# CONNECTORS.net
KiCad netlist of a schematic drawn in Altium Designer
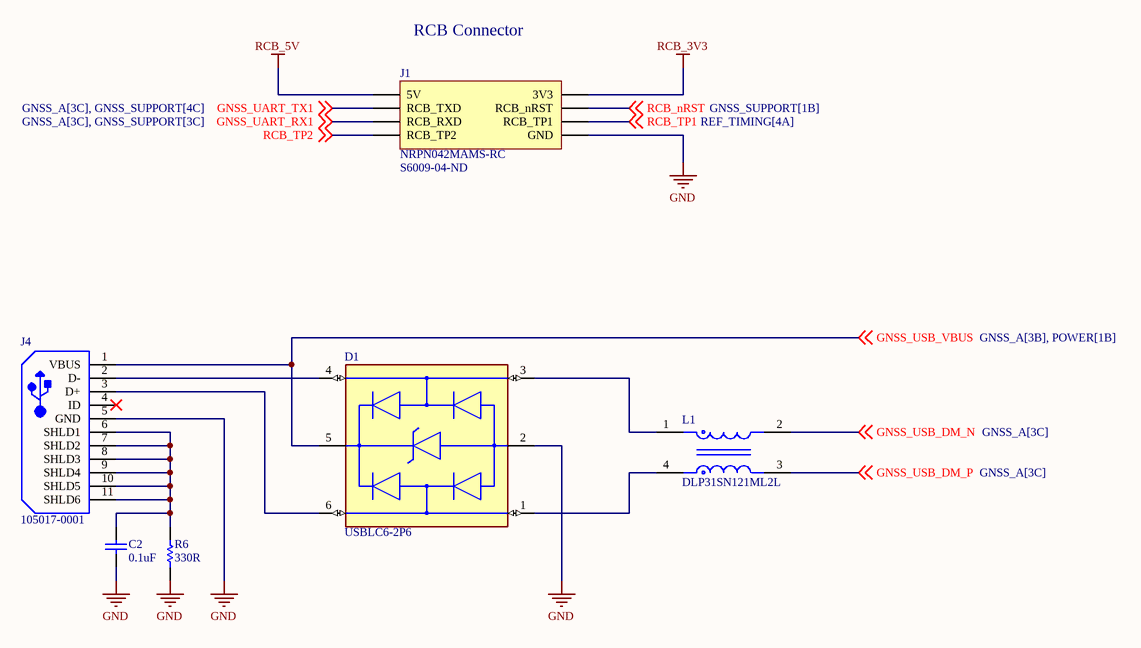
[diagram p0: CONNECTORS.SchDoc]

(export (version "E")
  (design (tool "Eeschema 10.0.6"))
  (components
    (comp (ref "C2")
      (value "0.1uF")
      (footprint "CAPC1005X56X25LL10T15")
      (fields
        (field (name "MANUFACTURER") "AVX Interconnect / Elco")
        (field (name "PART NUMBER") "04026D104KAT2A")
      )
      (libsource (lib "Altium Content Vault") (part "CAP"))
    )
    (comp (ref "D1")
      (value "USBLC6-2P6")
      (footprint "FP-SOT-666-MFG")
      (description "TVS DIODE 5.25V 17V SOT666")
      (libsource (lib "Altium Content Vault") (part "c871e55f7e3243d341edbd671b98d92"))
    )
    (comp (ref "J1")
      (value "NRPN042MAMS-RC")
      (footprint "NRPN042MAMS-RC")
      (description "Dual Row 8 Position 2 mm Pitch Surface Mount Header")
      (fields (field (name "MANUFACTURER") "Sullins") (field (name "SUPPLIER PART NUMBER 1") "S6009-04-ND"))
      (libsource (lib "GNSS_Receiver_Library") (part "NRPN042MAMS-RC"))
    )
    (comp (ref "J4")
      (value "105017-0001")
      (footprint "USB-MICRO-B_V")
      (fields (field (name "MANUFACTURER") "Molex"))
      (libsource (lib "Altium Content Vault") (part "USB-5-6SHLD"))
    )
    (comp (ref "L1")
      (value "DLP31SN121ML2L")
      (footprint "FP-DLP31SN-MFG")
      (description "CMC 100MA 2LN 120 OHM SMD")
      (fields (field (name "TOLERANCE") "20%"))
      (libsource (lib "Altium Content Vault") (part "fd0936f39cc88c8d3e52f875baaf0da"))
    )
    (comp (ref "R6")
      (value "330R")
      (footprint "RESC1005X40X25ML05T05")
      (fields (field (name "MANUFACTURER") "Panasonic") (field (name "PART NUMBER") "ERJ2RKF3300X"))
      (libsource (lib "Altium Content Vault") (part "RES"))
    )
  )
  (nets
    (net (code "1") (name "GND") (class "Default")
      (node (ref "C2") (pin "1") (pinfunction "1_1") (pintype "passive"))
      (node (ref "D1") (pin "2") (pinfunction "GND_2") (pintype "power_in"))
      (node (ref "J1") (pin "8") (pinfunction "GND_8") (pintype "passive"))
      (node (ref "J4") (pin "5") (pinfunction "GND_5") (pintype "passive"))
      (node (ref "R6") (pin "1") (pinfunction "1_1") (pintype "passive"))
    )
    (net (code "2") (name "GNSS_UART_RX1") (class "Default")
      (node (ref "J1") (pin "5") (pinfunction "RCB_RXD_5") (pintype "passive"))
    )
    (net (code "3") (name "GNSS_UART_TX1") (class "Default")
      (node (ref "J1") (pin "3") (pinfunction "RCB_TXD_3") (pintype "passive"))
    )
    (net (code "4") (name "GNSS_USB_DM_N") (class "Default")
      (node (ref "L1") (pin "2") (pinfunction "2_2") (pintype "passive"))
    )
    (net (code "5") (name "GNSS_USB_DM_P") (class "Default")
      (node (ref "L1") (pin "3") (pinfunction "3_3") (pintype "passive"))
    )
    (net (code "6") (name "GNSS_USB_VBUS") (class "Default")
      (node (ref "D1") (pin "5") (pinfunction "VBUS_5") (pintype "power_in"))
      (node (ref "J4") (pin "1") (pinfunction "VBUS_1") (pintype "passive"))
    )
    (net (code "7") (name "Net-(D1-I{slash}O1-Pad1)") (class "Default")
      (node (ref "D1") (pin "1") (pinfunction "I/O1_1") (pintype "bidirectional"))
      (node (ref "L1") (pin "4") (pinfunction "4_4") (pintype "passive"))
    )
    (net (code "8") (name "Net-(D1-I{slash}O2-Pad3)") (class "Default")
      (node (ref "D1") (pin "3") (pinfunction "I/O2_3") (pintype "bidirectional"))
      (node (ref "L1") (pin "1") (pinfunction "1_1") (pintype "passive"))
    )
    (net (code "9") (name "Net-(J4-D+)") (class "Default")
      (node (ref "D1") (pin "6") (pinfunction "I/O1_6") (pintype "bidirectional"))
      (node (ref "J4") (pin "3") (pinfunction "D+_3") (pintype "passive"))
    )
    (net (code "10") (name "Net-(J4-D-)") (class "Default")
      (node (ref "D1") (pin "4") (pinfunction "I/O2_4") (pintype "bidirectional"))
      (node (ref "J4") (pin "2") (pinfunction "D-_2") (pintype "passive"))
    )
    (net (code "11") (name "Net-(J4-SHLD1)") (class "Default")
      (node (ref "C2") (pin "2") (pinfunction "2_2") (pintype "passive"))
      (node (ref "J4") (pin "10") (pinfunction "SHLD5_10") (pintype "passive"))
      (node (ref "J4") (pin "11") (pinfunction "SHLD6_11") (pintype "passive"))
      (node (ref "J4") (pin "6") (pinfunction "SHLD1_6") (pintype "passive"))
      (node (ref "J4") (pin "7") (pinfunction "SHLD2_7") (pintype "passive"))
      (node (ref "J4") (pin "8") (pinfunction "SHLD3_8") (pintype "passive"))
      (node (ref "J4") (pin "9") (pinfunction "SHLD4_9") (pintype "passive"))
      (node (ref "R6") (pin "2") (pinfunction "2_2") (pintype "passive"))
    )
    (net (code "12") (name "RCB_3V3") (class "Default")
      (node (ref "J1") (pin "2") (pinfunction "3V3_2") (pintype "passive"))
    )
    (net (code "13") (name "RCB_5V") (class "Default")
      (node (ref "J1") (pin "1") (pinfunction "5V_1") (pintype "passive"))
    )
    (net (code "14") (name "RCB_TP1") (class "Default")
      (node (ref "J1") (pin "6") (pinfunction "RCB_TP1_6") (pintype "passive"))
    )
    (net (code "15") (name "RCB_TP2") (class "Default")
      (node (ref "J1") (pin "7") (pinfunction "RCB_TP2_7") (pintype "passive"))
    )
    (net (code "16") (name "RCB_nRST") (class "Default")
      (node (ref "J1") (pin "4") (pinfunction "RCB_nRST_4") (pintype "passive"))
    )
    (net (code "17") (name "unconnected-(J4-ID-Pad4)") (class "Default")
      (node (ref "J4") (pin "4") (pinfunction "ID_4") (pintype "passive+no_connect"))
    )
  )
)
